# r0ket_v2.net
KiCad netlist of a schematic drawn in EAGLE
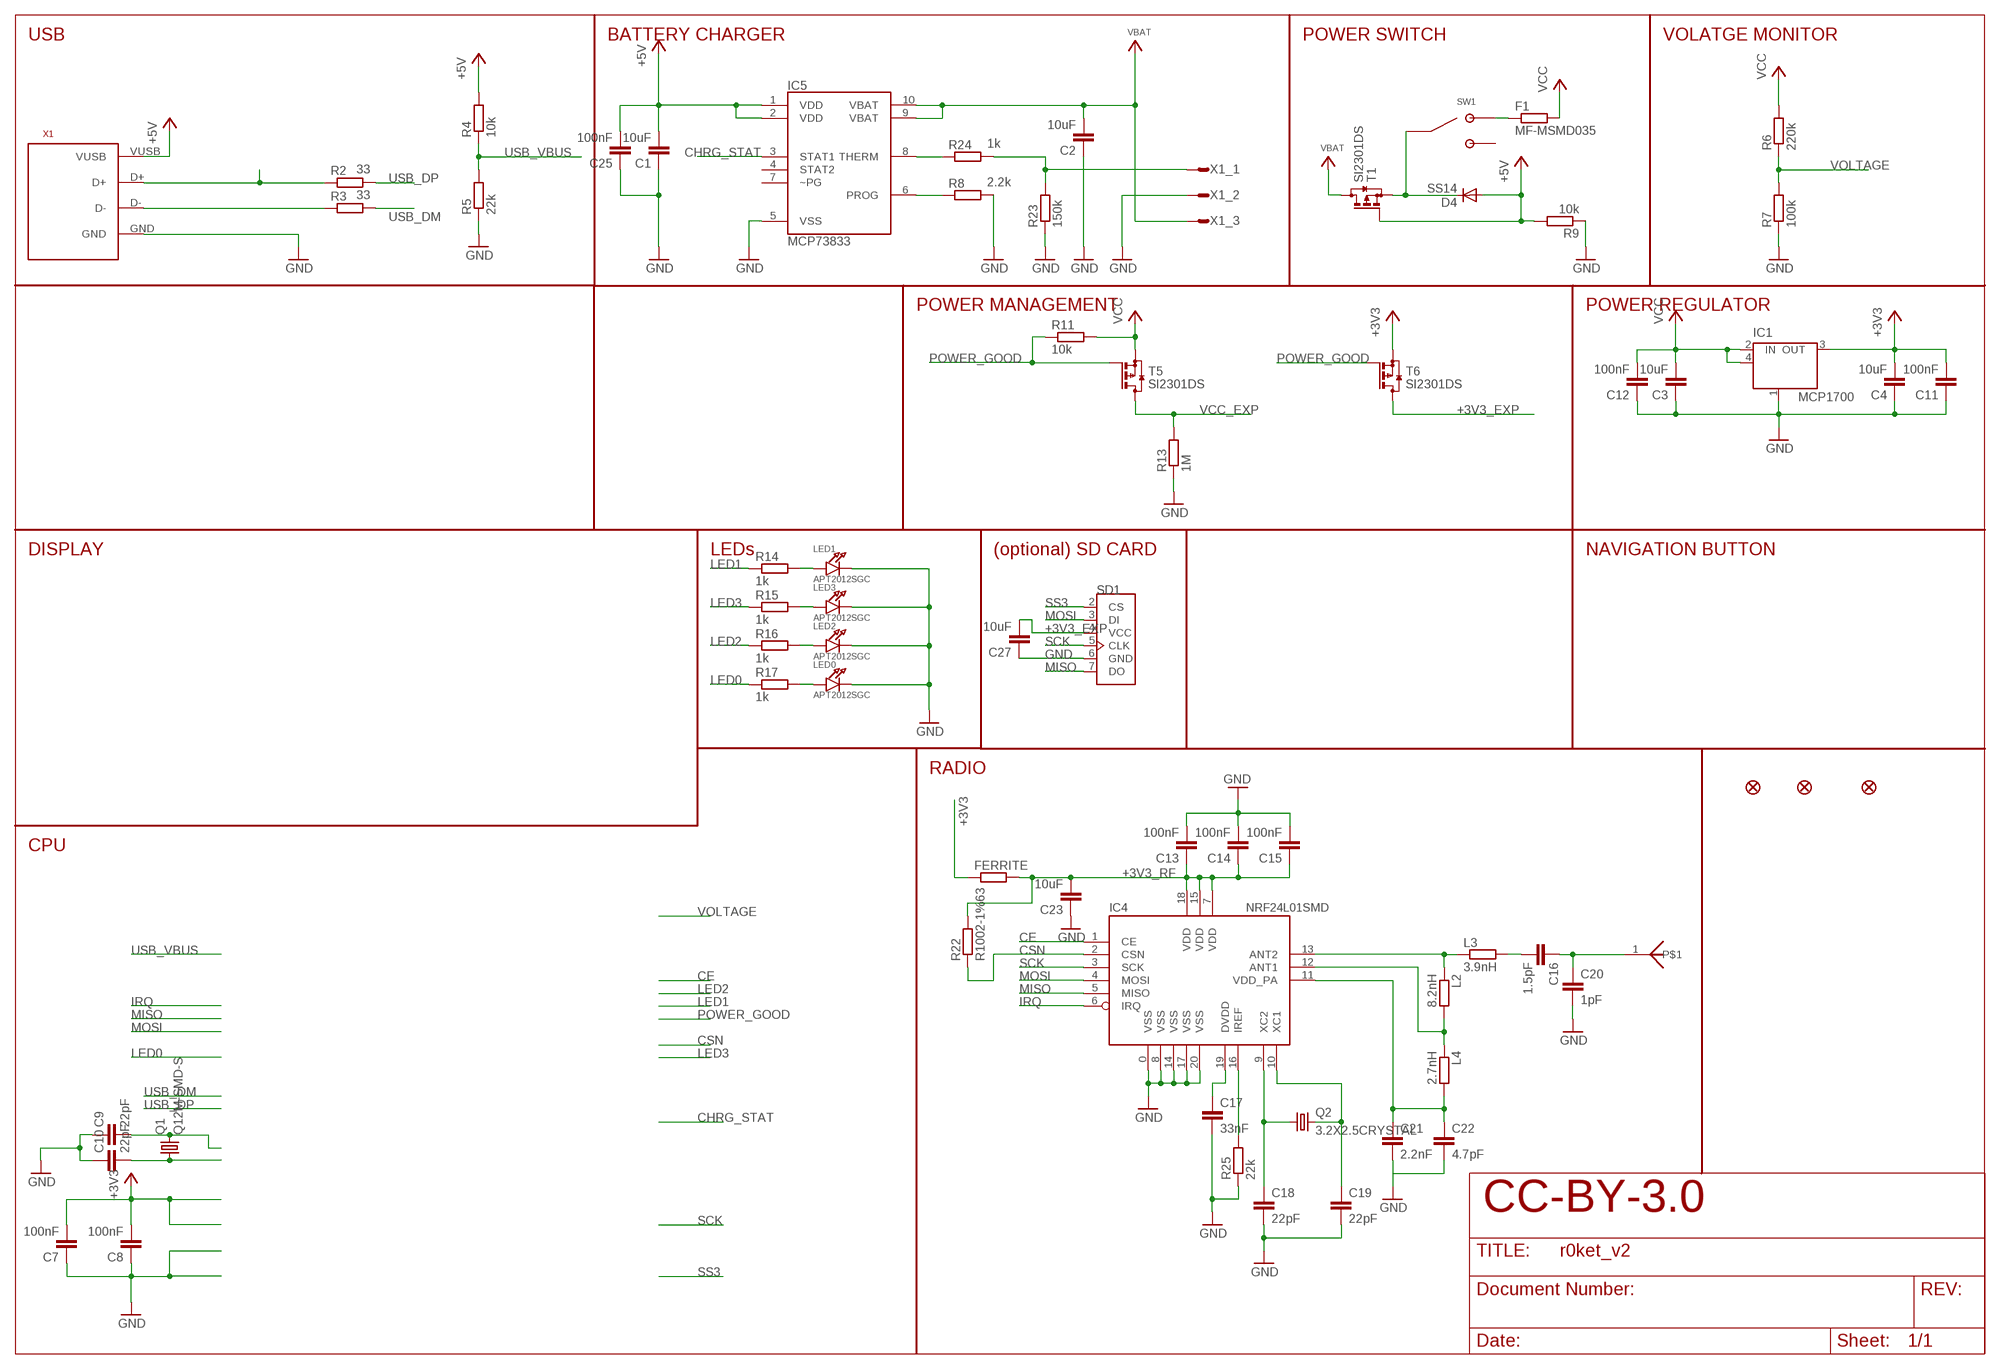
[diagram p0: schematic, sheet 1]

(export (version "E")
  (design (tool "Eeschema 10.0.6"))
  (components
    (comp (ref "ANT")
      (value "CHIPANTENNA")
      (footprint "eagle-import:CHIPANTENNA")
      (libsource (lib "eagle-import") (part "CHIPANTENNA"))
    )
    (comp (ref "C1")
      (value "10uF")
      (footprint "eagle-import:C0805K")
      (libsource (lib "eagle-import") (part "C-EUC0805K"))
    )
    (comp (ref "C2")
      (value "10uF")
      (footprint "eagle-import:C0805K")
      (libsource (lib "eagle-import") (part "C-EUC0805K"))
    )
    (comp (ref "C3")
      (value "10uF")
      (footprint "eagle-import:C0805K")
      (libsource (lib "eagle-import") (part "C-EUC0805K"))
    )
    (comp (ref "C4")
      (value "10uF")
      (footprint "eagle-import:C0805K")
      (libsource (lib "eagle-import") (part "C-EUC0805K"))
    )
    (comp (ref "C7")
      (value "100nF")
      (footprint "eagle-import:C0402K")
      (libsource (lib "eagle-import") (part "C-EUC0402K"))
    )
    (comp (ref "C8")
      (value "100nF")
      (footprint "eagle-import:C0402K")
      (libsource (lib "eagle-import") (part "C-EUC0402K"))
    )
    (comp (ref "C9")
      (value "22pF")
      (footprint "eagle-import:C0402K")
      (libsource (lib "eagle-import") (part "C-EUC0402K"))
    )
    (comp (ref "C10")
      (value "22pF")
      (footprint "eagle-import:C0402K")
      (libsource (lib "eagle-import") (part "C-EUC0402K"))
    )
    (comp (ref "C11")
      (value "100nF")
      (footprint "eagle-import:C0402K")
      (libsource (lib "eagle-import") (part "C-EUC0402K"))
    )
    (comp (ref "C12")
      (value "100nF")
      (footprint "eagle-import:C0402K")
      (libsource (lib "eagle-import") (part "C-EUC0402K"))
    )
    (comp (ref "C13")
      (value "100nF")
      (footprint "eagle-import:C0402K")
      (libsource (lib "eagle-import") (part "C-EUC0402K"))
    )
    (comp (ref "C14")
      (value "100nF")
      (footprint "eagle-import:C0402K")
      (libsource (lib "eagle-import") (part "C-EUC0402K"))
    )
    (comp (ref "C15")
      (value "100nF")
      (footprint "eagle-import:C0402K")
      (libsource (lib "eagle-import") (part "C-EUC0402K"))
    )
    (comp (ref "C16")
      (value "1.5pF")
      (footprint "eagle-import:C0402K")
      (libsource (lib "eagle-import") (part "C-EUC0402K"))
    )
    (comp (ref "C17")
      (value "33nF")
      (footprint "eagle-import:C0402K")
      (libsource (lib "eagle-import") (part "C-EUC0402K"))
    )
    (comp (ref "C18")
      (value "22pF")
      (footprint "eagle-import:C0402K")
      (libsource (lib "eagle-import") (part "C-EUC0402K"))
    )
    (comp (ref "C19")
      (value "22pF")
      (footprint "eagle-import:C0402K")
      (libsource (lib "eagle-import") (part "C-EUC0402K"))
    )
    (comp (ref "C20")
      (value "1pF")
      (footprint "eagle-import:C0402K")
      (libsource (lib "eagle-import") (part "C-EUC0402K"))
    )
    (comp (ref "C21")
      (value "2.2nF")
      (footprint "eagle-import:C0402K")
      (libsource (lib "eagle-import") (part "C-EUC0402K"))
    )
    (comp (ref "C22")
      (value "4.7pF")
      (footprint "eagle-import:C0402K")
      (libsource (lib "eagle-import") (part "C-EUC0402K"))
    )
    (comp (ref "C23")
      (value "10uF")
      (footprint "eagle-import:C0805K")
      (libsource (lib "eagle-import") (part "C-EUC0805K"))
    )
    (comp (ref "C25")
      (value "100nF")
      (footprint "eagle-import:C0402K")
      (libsource (lib "eagle-import") (part "C-EUC0402K"))
    )
    (comp (ref "C27")
      (value "10uF")
      (footprint "eagle-import:C0805K")
      (libsource (lib "eagle-import") (part "C-EUC0805K"))
    )
    (comp (ref "D4")
      (value "SS14")
      (footprint "eagle-import:SMB")
      (libsource (lib "eagle-import") (part "DIODE-SMB"))
    )
    (comp (ref "F1")
      (value "MF-MSMD035")
      (footprint "eagle-import:R1210")
      (libsource (lib "eagle-import") (part "R-EU_R1210"))
    )
    (comp (ref "FERRITE")
      (value "R-EU_R0805")
      (footprint "eagle-import:R0805")
      (libsource (lib "eagle-import") (part "R-EU_R0805"))
    )
    (comp (ref "FID1")
      (value "FIDUCIAL1.5X3")
      (footprint "eagle-import:FIDUCIAL-1.5X3")
      (libsource (lib "eagle-import") (part "FIDUCIAL1.5X3"))
    )
    (comp (ref "FID2")
      (value "FIDUCIAL1.5X3")
      (footprint "eagle-import:FIDUCIAL-1.5X3")
      (libsource (lib "eagle-import") (part "FIDUCIAL1.5X3"))
    )
    (comp (ref "FID3")
      (value "FIDUCIAL1.5X3")
      (footprint "eagle-import:FIDUCIAL-1.5X3")
      (libsource (lib "eagle-import") (part "FIDUCIAL1.5X3"))
    )
    (comp (ref "IC1")
      (value "MCP1700")
      (footprint "eagle-import:SOT89")
      (libsource (lib "eagle-import") (part "MCP1700"))
    )
    (comp (ref "IC4")
      (value "NRF24L01SMD")
      (footprint "eagle-import:QFN20")
      (libsource (lib "eagle-import") (part "NRF24L01SMD"))
    )
    (comp (ref "IC5")
      (value "MCP73833")
      (footprint "eagle-import:MSOP-10")
      (libsource (lib "eagle-import") (part "MCP73833"))
    )
    (comp (ref "L2")
      (value "8.2nH")
      (footprint "eagle-import:R0402")
      (libsource (lib "eagle-import") (part "R-EU_R0402"))
    )
    (comp (ref "L3")
      (value "3.9nH")
      (footprint "eagle-import:R0402")
      (libsource (lib "eagle-import") (part "R-EU_R0402"))
    )
    (comp (ref "L4")
      (value "2.7nH")
      (footprint "eagle-import:R0402")
      (libsource (lib "eagle-import") (part "R-EU_R0402"))
    )
    (comp (ref "LED0")
      (value "APT2012SGC")
      (footprint "eagle-import:CHIPLED_0805")
      (libsource (lib "eagle-import") (part "LED0805"))
    )
    (comp (ref "LED1")
      (value "APT2012SGC")
      (footprint "eagle-import:CHIPLED_0805")
      (libsource (lib "eagle-import") (part "LED0805"))
    )
    (comp (ref "LED2")
      (value "APT2012SGC")
      (footprint "eagle-import:CHIPLED_0805")
      (libsource (lib "eagle-import") (part "LED0805"))
    )
    (comp (ref "LED3")
      (value "APT2012SGC")
      (footprint "eagle-import:CHIPLED_0805")
      (libsource (lib "eagle-import") (part "LED0805"))
    )
    (comp (ref "Q1")
      (value "Q12M-SMD-S")
      (footprint "eagle-import:CTS406")
      (libsource (lib "eagle-import") (part "CRYSTALCTS406"))
    )
    (comp (ref "Q2")
      (value "3.2X2.5CRYSTAL")
      (footprint "eagle-import:CRYSTAL3.2X2.5")
      (libsource (lib "eagle-import") (part "3.2X2.5CRYSTAL"))
    )
    (comp (ref "R2")
      (value "33")
      (footprint "eagle-import:R0603")
      (libsource (lib "eagle-import") (part "R-EU_R0603"))
    )
    (comp (ref "R3")
      (value "33")
      (footprint "eagle-import:R0603")
      (libsource (lib "eagle-import") (part "R-EU_R0603"))
    )
    (comp (ref "R4")
      (value "10k")
      (footprint "eagle-import:R0603")
      (libsource (lib "eagle-import") (part "R-EU_R0603"))
    )
    (comp (ref "R5")
      (value "22k")
      (footprint "eagle-import:R0603")
      (libsource (lib "eagle-import") (part "R-EU_R0603"))
    )
    (comp (ref "R6")
      (value "220k")
      (footprint "eagle-import:R0603")
      (libsource (lib "eagle-import") (part "R-EU_R0603"))
    )
    (comp (ref "R7")
      (value "100k")
      (footprint "eagle-import:R0603")
      (libsource (lib "eagle-import") (part "R-EU_R0603"))
    )
    (comp (ref "R8")
      (value "2.2k")
      (footprint "eagle-import:R0603")
      (libsource (lib "eagle-import") (part "R-EU_R0603"))
    )
    (comp (ref "R9")
      (value "10k")
      (footprint "eagle-import:R0603")
      (libsource (lib "eagle-import") (part "R-EU_R0603"))
    )
    (comp (ref "R11")
      (value "10k")
      (footprint "eagle-import:R0603")
      (libsource (lib "eagle-import") (part "R-EU_R0603"))
    )
    (comp (ref "R13")
      (value "1M")
      (footprint "eagle-import:R0603")
      (libsource (lib "eagle-import") (part "R-EU_R0603"))
    )
    (comp (ref "R14")
      (value "1k")
      (footprint "eagle-import:R0603")
      (libsource (lib "eagle-import") (part "R-EU_R0603"))
    )
    (comp (ref "R15")
      (value "1k")
      (footprint "eagle-import:R0603")
      (libsource (lib "eagle-import") (part "R-EU_R0603"))
    )
    (comp (ref "R16")
      (value "1k")
      (footprint "eagle-import:R0603")
      (libsource (lib "eagle-import") (part "R-EU_R0603"))
    )
    (comp (ref "R17")
      (value "1k")
      (footprint "eagle-import:R0603")
      (libsource (lib "eagle-import") (part "R-EU_R0603"))
    )
    (comp (ref "R22")
      (value "R1002-1%63")
      (footprint "eagle-import:R0603")
      (libsource (lib "eagle-import") (part "R-EU_R0603"))
    )
    (comp (ref "R23")
      (value "150k")
      (footprint "eagle-import:R0603")
      (libsource (lib "eagle-import") (part "R-EU_R0603"))
    )
    (comp (ref "R24")
      (value "1k")
      (footprint "eagle-import:R0603")
      (libsource (lib "eagle-import") (part "R-EU_R0603"))
    )
    (comp (ref "R25")
      (value "22k")
      (footprint "eagle-import:R0603")
      (libsource (lib "eagle-import") (part "R-EU_R0603"))
    )
    (comp (ref "SD1")
      (value "MICROSD_SF-MICROSD")
      (footprint "eagle-import:MICROSD_MICROSD")
      (libsource (lib "eagle-import") (part "MICROSD_SF-MICROSD"))
    )
    (comp (ref "SW1")
      (value "JS102011SAQN")
      (footprint "eagle-import:JS102011SAQN")
      (libsource (lib "eagle-import") (part "JS102011SAQN"))
    )
    (comp (ref "T1")
      (value "SI2301DS")
      (footprint "eagle-import:SOT23")
      (libsource (lib "eagle-import") (part "BSS84"))
    )
    (comp (ref "T5")
      (value "SI2301DS")
      (footprint "eagle-import:SOT23")
      (libsource (lib "eagle-import") (part "BSS84"))
    )
    (comp (ref "T6")
      (value "SI2301DS")
      (footprint "eagle-import:SOT23")
      (libsource (lib "eagle-import") (part "BSS84"))
    )
    (comp (ref "X1")
      (value "MICROUSB")
      (footprint "eagle-import:MICROAB")
      (libsource (lib "eagle-import") (part "MICROUSB"))
    )
    (comp (ref "X1_")
      (value "JST-PH3")
      (footprint "eagle-import:JST-PH3")
      (libsource (lib "eagle-import") (part "JST-PH3"))
    )
  )
  (nets
    (net (code "1") (name "+3V3") (class "Default")
      (node (ref "C11") (pin "2") (pinfunction "2_2") (pintype "passive"))
      (node (ref "C4") (pin "2") (pinfunction "2_2") (pintype "passive"))
      (node (ref "C7") (pin "2") (pinfunction "2_2") (pintype "passive"))
      (node (ref "C8") (pin "2") (pinfunction "2_2") (pintype "passive"))
      (node (ref "FERRITE") (pin "1") (pinfunction "1_1") (pintype "passive"))
      (node (ref "IC1") (pin "3") (pinfunction "OUT_3") (pintype "passive"))
      (node (ref "T6") (pin "2") (pinfunction "S_2") (pintype "passive"))
    )
    (net (code "2") (name "+5V") (class "Default")
      (node (ref "C1") (pin "2") (pinfunction "2_2") (pintype "passive"))
      (node (ref "C25") (pin "2") (pinfunction "2_2") (pintype "passive"))
      (node (ref "D4") (pin "A") (pinfunction "A_A") (pintype "passive"))
      (node (ref "IC5") (pin "1") (pinfunction "VDD_1") (pintype "bidirectional"))
      (node (ref "IC5") (pin "2") (pinfunction "VDD_2") (pintype "bidirectional"))
      (node (ref "R4") (pin "2") (pinfunction "2_2") (pintype "passive"))
      (node (ref "R9") (pin "2") (pinfunction "2_2") (pintype "passive"))
      (node (ref "T1") (pin "1") (pinfunction "G_1") (pintype "passive"))
      (node (ref "X1") (pin "VUSB") (pinfunction "VUSB_VUSB") (pintype "bidirectional"))
    )
    (net (code "3") (name "/+3V3_EXP") (class "Default")
      (node (ref "C27") (pin "2") (pinfunction "2_2") (pintype "passive"))
      (node (ref "SD1") (pin "4") (pinfunction "VCC_4") (pintype "power_in"))
      (node (ref "T6") (pin "3") (pinfunction "D_3") (pintype "passive"))
    )
    (net (code "4") (name "/+3V3_RF") (class "Default")
      (node (ref "C13") (pin "1") (pinfunction "1_1") (pintype "passive"))
      (node (ref "C14") (pin "1") (pinfunction "1_1") (pintype "passive"))
      (node (ref "C15") (pin "1") (pinfunction "1_1") (pintype "passive"))
      (node (ref "C23") (pin "2") (pinfunction "2_2") (pintype "passive"))
      (node (ref "FERRITE") (pin "2") (pinfunction "2_2") (pintype "passive"))
      (node (ref "IC4") (pin "15") (pinfunction "VDD_15") (pintype "power_in"))
      (node (ref "IC4") (pin "18") (pinfunction "VDD_18") (pintype "power_in"))
      (node (ref "IC4") (pin "7") (pinfunction "VDD_7") (pintype "power_in"))
      (node (ref "R22") (pin "2") (pinfunction "2_2") (pintype "passive"))
    )
    (net (code "5") (name "/CE") (class "Default")
      (node (ref "IC4") (pin "1") (pinfunction "CE_1") (pintype "input"))
    )
    (net (code "6") (name "/CHRG_STAT") (class "Default")
      (node (ref "IC5") (pin "3") (pinfunction "STAT1_3") (pintype "bidirectional"))
    )
    (net (code "7") (name "/CSN") (class "Default")
      (node (ref "IC4") (pin "2") (pinfunction "CSN_2") (pintype "input"))
      (node (ref "R22") (pin "1") (pinfunction "1_1") (pintype "passive"))
    )
    (net (code "8") (name "/IRQ") (class "Default")
      (node (ref "IC4") (pin "6") (pinfunction "IRQ_6") (pintype "output"))
    )
    (net (code "9") (name "/LED0") (class "Default")
      (node (ref "R17") (pin "1") (pinfunction "1_1") (pintype "passive"))
    )
    (net (code "10") (name "/LED1") (class "Default")
      (node (ref "R14") (pin "1") (pinfunction "1_1") (pintype "passive"))
    )
    (net (code "11") (name "/LED2") (class "Default")
      (node (ref "R16") (pin "1") (pinfunction "1_1") (pintype "passive"))
    )
    (net (code "12") (name "/LED3") (class "Default")
      (node (ref "R15") (pin "1") (pinfunction "1_1") (pintype "passive"))
    )
    (net (code "13") (name "/MISO") (class "Default")
      (node (ref "IC4") (pin "5") (pinfunction "MISO_5") (pintype "output"))
      (node (ref "SD1") (pin "7") (pinfunction "DO_7") (pintype "output"))
    )
    (net (code "14") (name "/MOSI") (class "Default")
      (node (ref "IC4") (pin "4") (pinfunction "MOSI_4") (pintype "input"))
      (node (ref "SD1") (pin "3") (pinfunction "DI_3") (pintype "input"))
    )
    (net (code "15") (name "/POWER_GOOD") (class "Default")
      (node (ref "R11") (pin "1") (pinfunction "1_1") (pintype "passive"))
      (node (ref "T5") (pin "1") (pinfunction "G_1") (pintype "passive"))
      (node (ref "T6") (pin "1") (pinfunction "G_1") (pintype "passive"))
    )
    (net (code "16") (name "/SCK") (class "Default")
      (node (ref "IC4") (pin "3") (pinfunction "SCK_3") (pintype "input"))
      (node (ref "SD1") (pin "5") (pinfunction "CLK_5") (pintype "input"))
    )
    (net (code "17") (name "/SS3") (class "Default")
      (node (ref "SD1") (pin "2") (pinfunction "CS_2") (pintype "input"))
    )
    (net (code "18") (name "/USB_DM") (class "Default")
      (node (ref "R3") (pin "1") (pinfunction "1_1") (pintype "passive"))
    )
    (net (code "19") (name "/USB_DP") (class "Default")
      (node (ref "R2") (pin "1") (pinfunction "1_1") (pintype "passive"))
    )
    (net (code "20") (name "/USB_VBUS") (class "Default")
      (node (ref "R4") (pin "1") (pinfunction "1_1") (pintype "passive"))
      (node (ref "R5") (pin "2") (pinfunction "2_2") (pintype "passive"))
    )
    (net (code "21") (name "/VCC_EXP") (class "Default")
      (node (ref "R13") (pin "2") (pinfunction "2_2") (pintype "passive"))
      (node (ref "T5") (pin "3") (pinfunction "D_3") (pintype "passive"))
    )
    (net (code "22") (name "/VOLTAGE") (class "Default")
      (node (ref "R6") (pin "1") (pinfunction "1_1") (pintype "passive"))
      (node (ref "R7") (pin "2") (pinfunction "2_2") (pintype "passive"))
    )
    (net (code "23") (name "GND") (class "Default")
      (node (ref "C1") (pin "1") (pinfunction "1_1") (pintype "passive"))
      (node (ref "C10") (pin "1") (pinfunction "1_1") (pintype "passive"))
      (node (ref "C11") (pin "1") (pinfunction "1_1") (pintype "passive"))
      (node (ref "C12") (pin "1") (pinfunction "1_1") (pintype "passive"))
      (node (ref "C13") (pin "2") (pinfunction "2_2") (pintype "passive"))
      (node (ref "C14") (pin "2") (pinfunction "2_2") (pintype "passive"))
      (node (ref "C15") (pin "2") (pinfunction "2_2") (pintype "passive"))
      (node (ref "C17") (pin "2") (pinfunction "2_2") (pintype "passive"))
      (node (ref "C18") (pin "2") (pinfunction "2_2") (pintype "passive"))
      (node (ref "C19") (pin "2") (pinfunction "2_2") (pintype "passive"))
      (node (ref "C2") (pin "1") (pinfunction "1_1") (pintype "passive"))
      (node (ref "C20") (pin "2") (pinfunction "2_2") (pintype "passive"))
      (node (ref "C21") (pin "2") (pinfunction "2_2") (pintype "passive"))
      (node (ref "C22") (pin "2") (pinfunction "2_2") (pintype "passive"))
      (node (ref "C23") (pin "1") (pinfunction "1_1") (pintype "passive"))
      (node (ref "C25") (pin "1") (pinfunction "1_1") (pintype "passive"))
      (node (ref "C27") (pin "1") (pinfunction "1_1") (pintype "passive"))
      (node (ref "C3") (pin "1") (pinfunction "1_1") (pintype "passive"))
      (node (ref "C4") (pin "1") (pinfunction "1_1") (pintype "passive"))
      (node (ref "C7") (pin "1") (pinfunction "1_1") (pintype "passive"))
      (node (ref "C8") (pin "1") (pinfunction "1_1") (pintype "passive"))
      (node (ref "C9") (pin "1") (pinfunction "1_1") (pintype "passive"))
      (node (ref "IC1") (pin "1") (pinfunction "GND/ADJ_1") (pintype "input"))
      (node (ref "IC4") (pin "0") (pinfunction "VSS_0") (pintype "power_in"))
      (node (ref "IC4") (pin "14") (pinfunction "VSS_14") (pintype "power_in"))
      (node (ref "IC4") (pin "17") (pinfunction "VSS_17") (pintype "power_in"))
      (node (ref "IC4") (pin "20") (pinfunction "VSS_20") (pintype "power_in"))
      (node (ref "IC4") (pin "8") (pinfunction "VSS_8") (pintype "power_in"))
      (node (ref "IC5") (pin "5") (pinfunction "VSS_5") (pintype "bidirectional"))
      (node (ref "LED0") (pin "C") (pinfunction "C_C") (pintype "passive"))
      (node (ref "LED1") (pin "C") (pinfunction "C_C") (pintype "passive"))
      (node (ref "LED2") (pin "C") (pinfunction "C_C") (pintype "passive"))
      (node (ref "LED3") (pin "C") (pinfunction "C_C") (pintype "passive"))
      (node (ref "R13") (pin "1") (pinfunction "1_1") (pintype "passive"))
      (node (ref "R23") (pin "1") (pinfunction "1_1") (pintype "passive"))
      (node (ref "R25") (pin "1") (pinfunction "1_1") (pintype "passive"))
      (node (ref "R5") (pin "1") (pinfunction "1_1") (pintype "passive"))
      (node (ref "R7") (pin "1") (pinfunction "1_1") (pintype "passive"))
      (node (ref "R8") (pin "1") (pinfunction "1_1") (pintype "passive"))
      (node (ref "R9") (pin "1") (pinfunction "1_1") (pintype "passive"))
      (node (ref "SD1") (pin "6") (pinfunction "GND_6") (pintype "power_in"))
      (node (ref "X1") (pin "GND") (pinfunction "GND_GND") (pintype "bidirectional"))
      (node (ref "X1_") (pin "2") (pinfunction "1_2") (pintype "passive"))
    )
    (net (code "24") (name "Net-(ANT-P$1)") (class "Default")
      (node (ref "ANT") (pin "1") (pinfunction "P$1_1") (pintype "bidirectional"))
      (node (ref "C16") (pin "1") (pinfunction "1_1") (pintype "passive"))
      (node (ref "C20") (pin "1") (pinfunction "1_1") (pintype "passive"))
    )
    (net (code "25") (name "Net-(C10-Pad2)") (class "Default")
      (node (ref "C10") (pin "2") (pinfunction "2_2") (pintype "passive"))
      (node (ref "Q1") (pin "1") (pinfunction "1_1") (pintype "passive"))
    )
    (net (code "26") (name "Net-(C16-Pad2)") (class "Default")
      (node (ref "C16") (pin "2") (pinfunction "2_2") (pintype "passive"))
      (node (ref "L3") (pin "2") (pinfunction "2_2") (pintype "passive"))
    )
    (net (code "27") (name "Net-(F1-Pad1)") (class "Default")
      (node (ref "F1") (pin "1") (pinfunction "1_1") (pintype "passive"))
      (node (ref "SW1") (pin "1") (pinfunction "1_1") (pintype "passive"))
    )
    (net (code "28") (name "Net-(IC4-ANT1)") (class "Default")
      (node (ref "IC4") (pin "12") (pinfunction "ANT1_12") (pintype "output"))
      (node (ref "L2") (pin "2") (pinfunction "2_2") (pintype "passive"))
      (node (ref "L4") (pin "1") (pinfunction "1_1") (pintype "passive"))
    )
    (net (code "29") (name "Net-(IC4-ANT2)") (class "Default")
      (node (ref "IC4") (pin "13") (pinfunction "ANT2_13") (pintype "output"))
      (node (ref "L2") (pin "1") (pinfunction "1_1") (pintype "passive"))
      (node (ref "L3") (pin "1") (pinfunction "1_1") (pintype "passive"))
    )
    (net (code "30") (name "Net-(IC4-DVDD)") (class "Default")
      (node (ref "C17") (pin "1") (pinfunction "1_1") (pintype "passive"))
      (node (ref "IC4") (pin "19") (pinfunction "DVDD_19") (pintype "power_in"))
    )
    (net (code "31") (name "Net-(IC4-IREF)") (class "Default")
      (node (ref "IC4") (pin "16") (pinfunction "IREF_16") (pintype "input"))
      (node (ref "R25") (pin "2") (pinfunction "2_2") (pintype "passive"))
    )
    (net (code "32") (name "Net-(IC4-VDD_PA)") (class "Default")
      (node (ref "C21") (pin "1") (pinfunction "1_1") (pintype "passive"))
      (node (ref "C22") (pin "1") (pinfunction "1_1") (pintype "passive"))
      (node (ref "IC4") (pin "11") (pinfunction "VDD_PA_11") (pintype "power_in"))
      (node (ref "L4") (pin "2") (pinfunction "2_2") (pintype "passive"))
    )
    (net (code "33") (name "Net-(IC4-XC1)") (class "Default")
      (node (ref "C19") (pin "1") (pinfunction "1_1") (pintype "passive"))
      (node (ref "IC4") (pin "10") (pinfunction "XC1_10") (pintype "input"))
      (node (ref "Q2") (pin "3") (pinfunction "2_3") (pintype "passive"))
    )
    (net (code "34") (name "Net-(IC4-XC2)") (class "Default")
      (node (ref "C18") (pin "1") (pinfunction "1_1") (pintype "passive"))
      (node (ref "IC4") (pin "9") (pinfunction "XC2_9") (pintype "input"))
      (node (ref "Q2") (pin "1") (pinfunction "1_1") (pintype "passive"))
    )
    (net (code "35") (name "Net-(IC5-PROG)") (class "Default")
      (node (ref "IC5") (pin "6") (pinfunction "PROG_6") (pintype "bidirectional"))
      (node (ref "R8") (pin "2") (pinfunction "2_2") (pintype "passive"))
    )
    (net (code "36") (name "Net-(IC5-THERM)") (class "Default")
      (node (ref "IC5") (pin "8") (pinfunction "THERM_8") (pintype "bidirectional"))
      (node (ref "R24") (pin "2") (pinfunction "2_2") (pintype "passive"))
    )
    (net (code "37") (name "Net-(LED0-PadA)") (class "Default")
      (node (ref "LED0") (pin "A") (pinfunction "A_A") (pintype "passive"))
      (node (ref "R17") (pin "2") (pinfunction "2_2") (pintype "passive"))
    )
    (net (code "38") (name "Net-(LED1-PadA)") (class "Default")
      (node (ref "LED1") (pin "A") (pinfunction "A_A") (pintype "passive"))
      (node (ref "R14") (pin "2") (pinfunction "2_2") (pintype "passive"))
    )
    (net (code "39") (name "Net-(LED2-PadA)") (class "Default")
      (node (ref "LED2") (pin "A") (pinfunction "A_A") (pintype "passive"))
      (node (ref "R16") (pin "2") (pinfunction "2_2") (pintype "passive"))
    )
    (net (code "40") (name "Net-(LED3-PadA)") (class "Default")
      (node (ref "LED3") (pin "A") (pinfunction "A_A") (pintype "passive"))
      (node (ref "R15") (pin "2") (pinfunction "2_2") (pintype "passive"))
    )
    (net (code "41") (name "Net-(Q1-2)") (class "Default")
      (node (ref "C9") (pin "2") (pinfunction "2_2") (pintype "passive"))
      (node (ref "Q1") (pin "3") (pinfunction "2_3") (pintype "passive"))
    )
    (net (code "42") (name "Net-(R2-Pad2)") (class "Default")
      (node (ref "R2") (pin "2") (pinfunction "2_2") (pintype "passive"))
      (node (ref "X1") (pin "D+") (pinfunction "D+_D+") (pintype "bidirectional"))
    )
    (net (code "43") (name "Net-(R3-Pad2)") (class "Default")
      (node (ref "R3") (pin "2") (pinfunction "2_2") (pintype "passive"))
      (node (ref "X1") (pin "D-") (pinfunction "D-_D-") (pintype "bidirectional"))
    )
    (net (code "44") (name "Net-(R23-Pad2)") (class "Default")
      (node (ref "R23") (pin "2") (pinfunction "2_2") (pintype "passive"))
      (node (ref "R24") (pin "1") (pinfunction "1_1") (pintype "passive"))
      (node (ref "X1_") (pin "1") (pinfunction "1_1") (pintype "passive"))
    )
    (net (code "45") (name "Net-(T1-S)") (class "Default")
      (node (ref "D4") (pin "C") (pinfunction "C_C") (pintype "passive"))
      (node (ref "SW1") (pin "2") (pinfunction "2_2") (pintype "passive"))
      (node (ref "T1") (pin "2") (pinfunction "S_2") (pintype "passive"))
    )
    (net (code "46") (name "VBAT") (class "Default")
      (node (ref "C2") (pin "2") (pinfunction "2_2") (pintype "passive"))
      (node (ref "IC5") (pin "10") (pinfunction "VBAT_10") (pintype "bidirectional"))
      (node (ref "IC5") (pin "9") (pinfunction "VBAT_9") (pintype "bidirectional"))
      (node (ref "T1") (pin "3") (pinfunction "D_3") (pintype "passive"))
      (node (ref "X1_") (pin "3") (pinfunction "1_3") (pintype "passive"))
    )
    (net (code "47") (name "VCC") (class "Default")
      (node (ref "C12") (pin "2") (pinfunction "2_2") (pintype "passive"))
      (node (ref "C3") (pin "2") (pinfunction "2_2") (pintype "passive"))
      (node (ref "F1") (pin "2") (pinfunction "2_2") (pintype "passive"))
      (node (ref "IC1") (pin "2") (pinfunction "IN_2") (pintype "input"))
      (node (ref "IC1") (pin "4") (pinfunction "IN_4") (pintype "input"))
      (node (ref "R11") (pin "2") (pinfunction "2_2") (pintype "passive"))
      (node (ref "R6") (pin "2") (pinfunction "2_2") (pintype "passive"))
      (node (ref "T5") (pin "2") (pinfunction "S_2") (pintype "passive"))
    )
    (net (code "48") (name "unconnected-(IC5-STAT2-Pad4)") (class "Default")
      (node (ref "IC5") (pin "4") (pinfunction "STAT2_4") (pintype "bidirectional"))
    )
    (net (code "49") (name "unconnected-(IC5-~{PG}-Pad7)") (class "Default")
      (node (ref "IC5") (pin "7") (pinfunction "~{PG}_7") (pintype "bidirectional"))
    )
    (net (code "50") (name "unconnected-(SW1-Pad3)") (class "Default")
      (node (ref "SW1") (pin "3") (pinfunction "3_3") (pintype "passive"))
    )
  )
)
